# elderstep.net
KiCad netlist of a schematic drawn in EAGLE
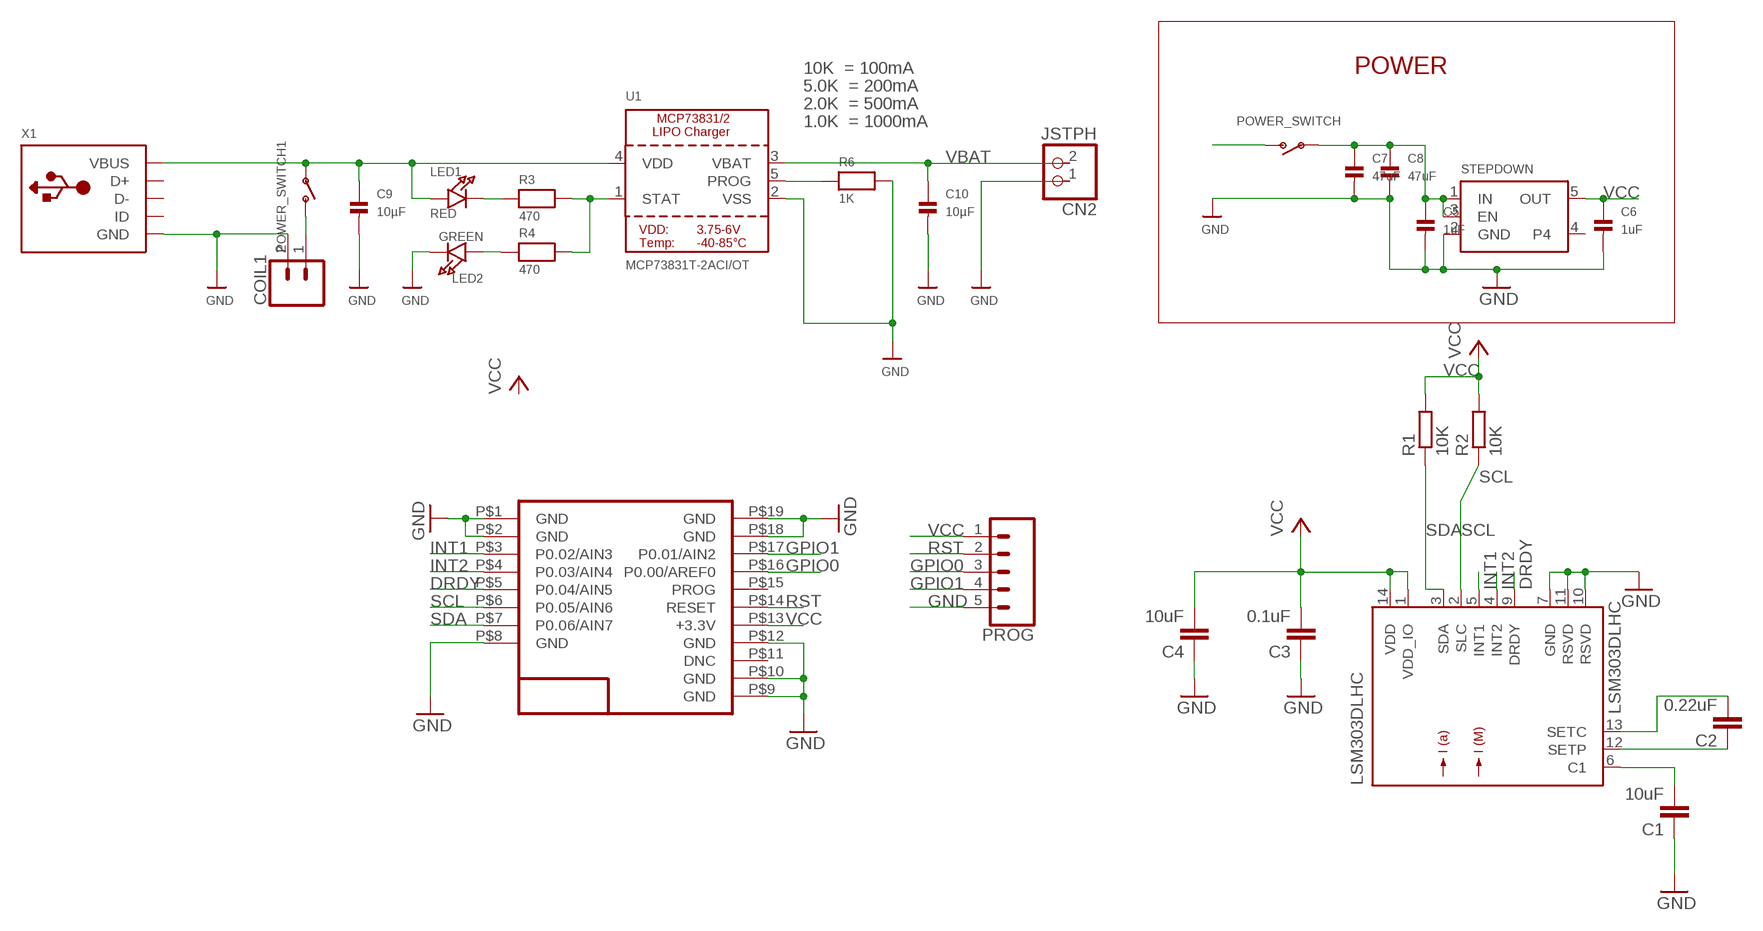
[diagram p0: schematic, sheet 1]

(export (version "E")
  (design (tool "Eeschema 10.0.6"))
  (components
    (comp (ref "C1")
      (value "10uF")
      (footprint "eagle-import:C0805")
      (libsource (lib "eagle-import") (part "C-EUC0805"))
    )
    (comp (ref "C2")
      (value "0.22uF")
      (footprint "eagle-import:C0805")
      (libsource (lib "eagle-import") (part "C-EUC0805"))
    )
    (comp (ref "C3")
      (value "0.1uF")
      (footprint "eagle-import:C0805")
      (libsource (lib "eagle-import") (part "C-EUC0805"))
    )
    (comp (ref "C4")
      (value "10uF")
      (footprint "eagle-import:C0805")
      (libsource (lib "eagle-import") (part "C-EUC0805"))
    )
    (comp (ref "C5")
      (value "1uF")
      (footprint "eagle-import:0603")
      (libsource (lib "eagle-import") (part "CAP_CERAMIC0603"))
    )
    (comp (ref "C6")
      (value "1uF")
      (footprint "eagle-import:0603")
      (libsource (lib "eagle-import") (part "CAP_CERAMIC0603"))
    )
    (comp (ref "C7")
      (value "47uF")
      (footprint "eagle-import:0805")
      (libsource (lib "eagle-import") (part "CAP_CERAMIC0805"))
    )
    (comp (ref "C8")
      (value "47uF")
      (footprint "eagle-import:0805")
      (libsource (lib "eagle-import") (part "CAP_CERAMIC0805"))
    )
    (comp (ref "C9")
      (value "10µF")
      (footprint "eagle-import:0805")
      (libsource (lib "eagle-import") (part "CAP_CERAMIC0805"))
    )
    (comp (ref "C10")
      (value "10µF")
      (footprint "eagle-import:0805")
      (libsource (lib "eagle-import") (part "CAP_CERAMIC0805"))
    )
    (comp (ref "CN2")
      (value "JSTPH")
      (footprint "eagle-import:JSTPH2")
      (libsource (lib "eagle-import") (part "JST_2PIN"))
    )
    (comp (ref "COIL1")
      (value "CONN_02")
      (footprint "eagle-import:1X02")
      (libsource (lib "eagle-import") (part "CONN_02"))
    )
    (comp (ref "LED1")
      (value "RED")
      (footprint "eagle-import:CHIPLED_0805")
      (libsource (lib "eagle-import") (part "LED0805"))
    )
    (comp (ref "LED2")
      (value "GREEN")
      (footprint "eagle-import:CHIPLED_0805")
      (libsource (lib "eagle-import") (part "LED0805"))
    )
    (comp (ref "LSM303DLHC")
      (value "LSM303DLHC")
      (footprint "eagle-import:LGA-14")
      (libsource (lib "eagle-import") (part "LSM303DLHC"))
    )
    (comp (ref "POWER_SWITCH")
      (value "SWITCH_SPST")
      (footprint "eagle-import:SPST_SMT_19192")
      (libsource (lib "eagle-import") (part "SWITCH_SPST"))
    )
    (comp (ref "POWER_SWITCH1")
      (value "SWITCH_SPST")
      (footprint "eagle-import:SPST_SMT_19192")
      (libsource (lib "eagle-import") (part "SWITCH_SPST"))
    )
    (comp (ref "PROG")
      (value "CONN_05")
      (footprint "eagle-import:1X05")
      (libsource (lib "eagle-import") (part "CONN_05"))
    )
    (comp (ref "R1")
      (value "10K")
      (footprint "eagle-import:R0805")
      (libsource (lib "eagle-import") (part "R-EU_R0805"))
    )
    (comp (ref "R2")
      (value "10K")
      (footprint "eagle-import:R0805")
      (libsource (lib "eagle-import") (part "R-EU_R0805"))
    )
    (comp (ref "R3")
      (value "470")
      (footprint "eagle-import:0805")
      (libsource (lib "eagle-import") (part "RESISTOR0805"))
    )
    (comp (ref "R4")
      (value "470")
      (footprint "eagle-import:0805")
      (libsource (lib "eagle-import") (part "RESISTOR0805"))
    )
    (comp (ref "R6")
      (value "1K")
      (footprint "eagle-import:0805")
      (libsource (lib "eagle-import") (part "RESISTOR0805"))
    )
    (comp (ref "RFD22301")
      (value "RFD22301")
      (footprint "eagle-import:RFD21733")
      (libsource (lib "eagle-import") (part "RFD22301"))
    )
    (comp (ref "STEPDOWN")
      (value "VREG_SOT23-5")
      (footprint "eagle-import:SOT23-5")
      (libsource (lib "eagle-import") (part "VREG_SOT23-5"))
    )
    (comp (ref "U1")
      (value "MCP73831T-2ACI/OT")
      (footprint "eagle-import:SOT23-5")
      (libsource (lib "eagle-import") (part "MCP73831/2"))
    )
    (comp (ref "X1")
      (value "USBMICRO_20329")
      (footprint "eagle-import:4UCONN_20329")
      (libsource (lib "eagle-import") (part "USBMICRO_20329"))
    )
  )
  (nets
    (net (code "1") (name "/DRDY") (class "Default")
      (node (ref "LSM303DLHC") (pin "9") (pinfunction "DRDY_9") (pintype "bidirectional"))
      (node (ref "RFD22301") (pin "P$5") (pinfunction "P0.04/AIN5_P$5") (pintype "bidirectional"))
    )
    (net (code "2") (name "/GPIO0") (class "Default")
      (node (ref "PROG") (pin "3") (pinfunction "3_3") (pintype "passive"))
      (node (ref "RFD22301") (pin "P$16") (pinfunction "P0.00/AREF0_P$16") (pintype "bidirectional"))
    )
    (net (code "3") (name "/GPIO1") (class "Default")
      (node (ref "PROG") (pin "4") (pinfunction "4_4") (pintype "passive"))
      (node (ref "RFD22301") (pin "P$17") (pinfunction "P0.01/AIN2_P$17") (pintype "bidirectional"))
    )
    (net (code "4") (name "/INT1") (class "Default")
      (node (ref "LSM303DLHC") (pin "5") (pinfunction "INT1_5") (pintype "bidirectional"))
      (node (ref "RFD22301") (pin "P$3") (pinfunction "P0.02/AIN3_P$3") (pintype "bidirectional"))
    )
    (net (code "5") (name "/INT2") (class "Default")
      (node (ref "LSM303DLHC") (pin "4") (pinfunction "INT2_4") (pintype "bidirectional"))
      (node (ref "RFD22301") (pin "P$4") (pinfunction "P0.03/AIN4_P$4") (pintype "bidirectional"))
    )
    (net (code "6") (name "/RST") (class "Default")
      (node (ref "PROG") (pin "2") (pinfunction "2_2") (pintype "passive"))
      (node (ref "RFD22301") (pin "P$14") (pinfunction "RESET_P$14") (pintype "bidirectional"))
    )
    (net (code "7") (name "/SCL") (class "Default")
      (node (ref "LSM303DLHC") (pin "2") (pinfunction "SLC_2") (pintype "bidirectional"))
      (node (ref "R2") (pin "1") (pinfunction "1_1") (pintype "passive"))
      (node (ref "RFD22301") (pin "P$6") (pinfunction "P0.05/AIN6_P$6") (pintype "bidirectional"))
    )
    (net (code "8") (name "/SDA") (class "Default")
      (node (ref "LSM303DLHC") (pin "3") (pinfunction "SDA_3") (pintype "bidirectional"))
      (node (ref "R1") (pin "1") (pinfunction "1_1") (pintype "passive"))
      (node (ref "RFD22301") (pin "P$7") (pinfunction "P0.06/AIN7_P$7") (pintype "bidirectional"))
    )
    (net (code "9") (name "/VBAT") (class "Default")
      (node (ref "C10") (pin "1") (pinfunction "P$1_1") (pintype "passive"))
      (node (ref "CN2") (pin "2") (pinfunction "2_2") (pintype "passive"))
      (node (ref "POWER_SWITCH") (pin "C") (pinfunction "S_C") (pintype "passive"))
      (node (ref "U1") (pin "3") (pinfunction "VBAT_3") (pintype "power_in"))
    )
    (net (code "10") (name "GND") (class "Default")
      (node (ref "C1") (pin "1") (pinfunction "1_1") (pintype "passive"))
      (node (ref "C10") (pin "2") (pinfunction "P$2_2") (pintype "passive"))
      (node (ref "C3") (pin "1") (pinfunction "1_1") (pintype "passive"))
      (node (ref "C4") (pin "1") (pinfunction "1_1") (pintype "passive"))
      (node (ref "C5") (pin "2") (pinfunction "P$2_2") (pintype "passive"))
      (node (ref "C6") (pin "2") (pinfunction "P$2_2") (pintype "passive"))
      (node (ref "C7") (pin "2") (pinfunction "P$2_2") (pintype "passive"))
      (node (ref "C8") (pin "2") (pinfunction "P$2_2") (pintype "passive"))
      (node (ref "C9") (pin "2") (pinfunction "P$2_2") (pintype "passive"))
      (node (ref "CN2") (pin "1") (pinfunction "1_1") (pintype "passive"))
      (node (ref "COIL1") (pin "2") (pinfunction "2_2") (pintype "passive"))
      (node (ref "LED2") (pin "C") (pinfunction "C_C") (pintype "passive"))
      (node (ref "LSM303DLHC") (pin "10") (pinfunction "RSVD_10") (pintype "passive"))
      (node (ref "LSM303DLHC") (pin "11") (pinfunction "RSVD_11") (pintype "passive"))
      (node (ref "LSM303DLHC") (pin "7") (pinfunction "GND_7") (pintype "power_in"))
      (node (ref "PROG") (pin "5") (pinfunction "5_5") (pintype "passive"))
      (node (ref "R6") (pin "2") (pinfunction "2_2") (pintype "passive"))
      (node (ref "RFD22301") (pin "P$1") (pinfunction "GND_P$1") (pintype "bidirectional"))
      (node (ref "RFD22301") (pin "P$10") (pinfunction "GND_P$10") (pintype "bidirectional"))
      (node (ref "RFD22301") (pin "P$12") (pinfunction "GND_P$12") (pintype "bidirectional"))
      (node (ref "RFD22301") (pin "P$18") (pinfunction "GND_P$18") (pintype "bidirectional"))
      (node (ref "RFD22301") (pin "P$19") (pinfunction "GND_P$19") (pintype "bidirectional"))
      (node (ref "RFD22301") (pin "P$2") (pinfunction "GND_P$2") (pintype "bidirectional"))
      (node (ref "RFD22301") (pin "P$8") (pinfunction "GND_P$8") (pintype "bidirectional"))
      (node (ref "RFD22301") (pin "P$9") (pinfunction "GND_P$9") (pintype "bidirectional"))
      (node (ref "STEPDOWN") (pin "2") (pinfunction "GND_2") (pintype "bidirectional"))
      (node (ref "U1") (pin "2") (pinfunction "VSS_2") (pintype "power_in"))
      (node (ref "X1") (pin "BASE@1") (pinfunction "GND_BASE@1") (pintype "power_in"))
      (node (ref "X1") (pin "BASE@2") (pinfunction "GND_BASE@2") (pintype "power_in"))
      (node (ref "X1") (pin "GND") (pinfunction "GND_GND") (pintype "power_in"))
      (node (ref "X1") (pin "SPRT@1") (pinfunction "GND_SPRT@1") (pintype "power_in"))
      (node (ref "X1") (pin "SPRT@2") (pinfunction "GND_SPRT@2") (pintype "power_in"))
      (node (ref "X1") (pin "SPRT@3") (pinfunction "GND_SPRT@3") (pintype "power_in"))
      (node (ref "X1") (pin "SPRT@4") (pinfunction "GND_SPRT@4") (pintype "power_in"))
    )
    (net (code "11") (name "Net-(C5-P$1)") (class "Default")
      (node (ref "C5") (pin "1") (pinfunction "P$1_1") (pintype "passive"))
      (node (ref "C7") (pin "1") (pinfunction "P$1_1") (pintype "passive"))
      (node (ref "C8") (pin "1") (pinfunction "P$1_1") (pintype "passive"))
      (node (ref "POWER_SWITCH") (pin "B") (pinfunction "P_B") (pintype "passive"))
      (node (ref "STEPDOWN") (pin "1") (pinfunction "IN_1") (pintype "bidirectional"))
      (node (ref "STEPDOWN") (pin "3") (pinfunction "EN_3") (pintype "bidirectional"))
    )
    (net (code "12") (name "Net-(C9-P$1)") (class "Default")
      (node (ref "C9") (pin "1") (pinfunction "P$1_1") (pintype "passive"))
      (node (ref "LED1") (pin "A") (pinfunction "A_A") (pintype "passive"))
      (node (ref "POWER_SWITCH1") (pin "B") (pinfunction "P_B") (pintype "passive"))
      (node (ref "U1") (pin "4") (pinfunction "VDD_4") (pintype "power_in"))
      (node (ref "X1") (pin "VBUS") (pinfunction "VBUS_VBUS") (pintype "power_in"))
    )
    (net (code "13") (name "Net-(LED1-PadC)") (class "Default")
      (node (ref "LED1") (pin "C") (pinfunction "C_C") (pintype "passive"))
      (node (ref "R3") (pin "1") (pinfunction "1_1") (pintype "passive"))
    )
    (net (code "14") (name "Net-(LED2-PadA)") (class "Default")
      (node (ref "LED2") (pin "A") (pinfunction "A_A") (pintype "passive"))
      (node (ref "R4") (pin "1") (pinfunction "1_1") (pintype "passive"))
    )
    (net (code "15") (name "Net-(LSM303DLHC-C1)") (class "Default")
      (node (ref "C1") (pin "2") (pinfunction "2_2") (pintype "passive"))
      (node (ref "LSM303DLHC") (pin "6") (pinfunction "C1_6") (pintype "passive"))
    )
    (net (code "16") (name "Net-(LSM303DLHC-SETC)") (class "Default")
      (node (ref "C2") (pin "2") (pinfunction "2_2") (pintype "passive"))
      (node (ref "LSM303DLHC") (pin "13") (pinfunction "SETC_13") (pintype "passive"))
    )
    (net (code "17") (name "Net-(LSM303DLHC-SETP)") (class "Default")
      (node (ref "C2") (pin "1") (pinfunction "1_1") (pintype "passive"))
      (node (ref "LSM303DLHC") (pin "12") (pinfunction "SETP_12") (pintype "passive"))
    )
    (net (code "18") (name "Net-(POWER_SWITCH1-S)") (class "Default")
      (node (ref "COIL1") (pin "1") (pinfunction "1_1") (pintype "passive"))
      (node (ref "POWER_SWITCH1") (pin "C") (pinfunction "S_C") (pintype "passive"))
    )
    (net (code "19") (name "Net-(U1-PROG)") (class "Default")
      (node (ref "R6") (pin "1") (pinfunction "1_1") (pintype "passive"))
      (node (ref "U1") (pin "5") (pinfunction "PROG_5") (pintype "input"))
    )
    (net (code "20") (name "Net-(U1-STAT)") (class "Default")
      (node (ref "R3") (pin "2") (pinfunction "2_2") (pintype "passive"))
      (node (ref "R4") (pin "2") (pinfunction "2_2") (pintype "passive"))
      (node (ref "U1") (pin "1") (pinfunction "STAT_1") (pintype "output"))
    )
    (net (code "21") (name "VCC") (class "Default")
      (node (ref "C3") (pin "2") (pinfunction "2_2") (pintype "passive"))
      (node (ref "C4") (pin "2") (pinfunction "2_2") (pintype "passive"))
      (node (ref "C6") (pin "1") (pinfunction "P$1_1") (pintype "passive"))
      (node (ref "LSM303DLHC") (pin "1") (pinfunction "VDD_IO_1") (pintype "power_in"))
      (node (ref "LSM303DLHC") (pin "14") (pinfunction "VDD_14") (pintype "power_in"))
      (node (ref "PROG") (pin "1") (pinfunction "1_1") (pintype "passive"))
      (node (ref "R1") (pin "2") (pinfunction "2_2") (pintype "passive"))
      (node (ref "R2") (pin "2") (pinfunction "2_2") (pintype "passive"))
      (node (ref "RFD22301") (pin "P$13") (pinfunction "+3.3V_P$13") (pintype "bidirectional"))
      (node (ref "STEPDOWN") (pin "5") (pinfunction "OUT_5") (pintype "bidirectional"))
    )
    (net (code "22") (name "unconnected-(RFD22301-DNC-PadP$11)") (class "Default")
      (node (ref "RFD22301") (pin "P$11") (pinfunction "DNC_P$11") (pintype "bidirectional"))
    )
    (net (code "23") (name "unconnected-(RFD22301-PROG-PadP$15)") (class "Default")
      (node (ref "RFD22301") (pin "P$15") (pinfunction "PROG_P$15") (pintype "bidirectional"))
    )
    (net (code "24") (name "unconnected-(STEPDOWN-P4-Pad4)") (class "Default")
      (node (ref "STEPDOWN") (pin "4") (pinfunction "P4_4") (pintype "bidirectional"))
    )
    (net (code "25") (name "unconnected-(X1-PadD+)") (class "Default")
      (node (ref "X1") (pin "D+") (pinfunction "D+_D+") (pintype "bidirectional"))
    )
    (net (code "26") (name "unconnected-(X1-PadD-)") (class "Default")
      (node (ref "X1") (pin "D-") (pinfunction "D-_D-") (pintype "bidirectional"))
    )
    (net (code "27") (name "unconnected-(X1-PadID)") (class "Default")
      (node (ref "X1") (pin "ID") (pinfunction "ID_ID") (pintype "bidirectional"))
    )
  )
)
